# input_matrix.net
KiCad netlist of a schematic drawn in Altium Designer
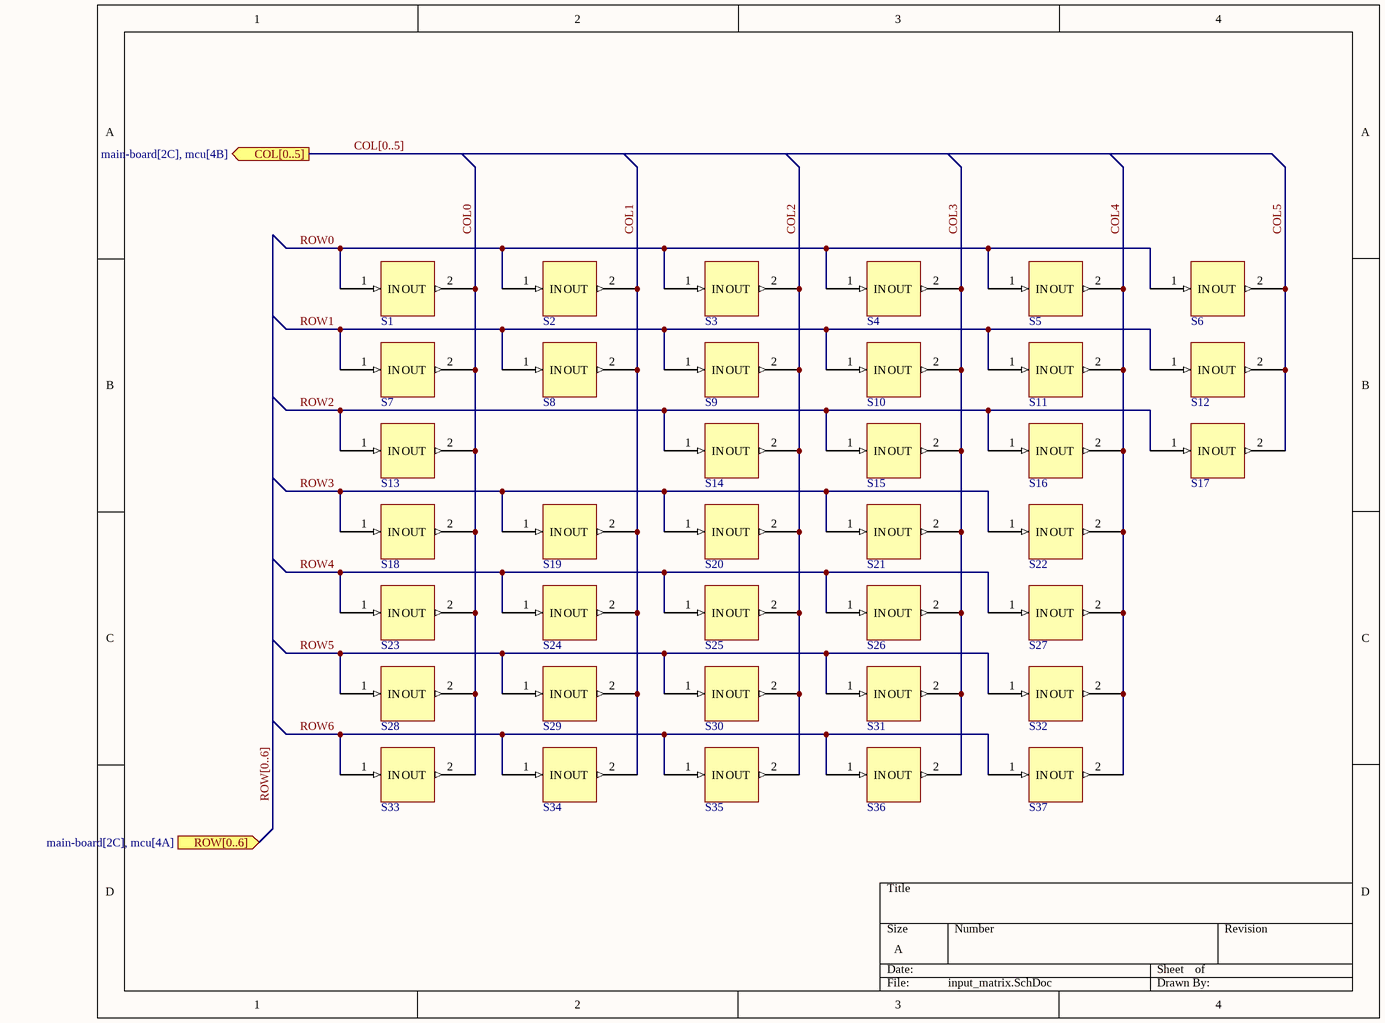
[diagram p0: input_matrix.SchDoc]

(export (version "E")
  (design (tool "Eeschema 10.0.6"))
  (components
    (comp (ref "S1")
      (value "temp_switch")
      (footprint "PCBComponent_1")
      (libsource (lib "button") (part "temp_switch"))
    )
    (comp (ref "S2")
      (value "temp_switch")
      (footprint "PCBComponent_1")
      (libsource (lib "button") (part "temp_switch"))
    )
    (comp (ref "S3")
      (value "temp_switch")
      (footprint "PCBComponent_1")
      (libsource (lib "button") (part "temp_switch"))
    )
    (comp (ref "S4")
      (value "temp_switch")
      (footprint "PCBComponent_1")
      (libsource (lib "button") (part "temp_switch"))
    )
    (comp (ref "S5")
      (value "temp_switch")
      (footprint "PCBComponent_1")
      (libsource (lib "button") (part "temp_switch"))
    )
    (comp (ref "S6")
      (value "temp_switch")
      (footprint "PCBComponent_1")
      (libsource (lib "button") (part "temp_switch"))
    )
    (comp (ref "S7")
      (value "temp_switch")
      (footprint "PCBComponent_1")
      (libsource (lib "button") (part "temp_switch"))
    )
    (comp (ref "S8")
      (value "temp_switch")
      (footprint "PCBComponent_1")
      (libsource (lib "button") (part "temp_switch"))
    )
    (comp (ref "S9")
      (value "temp_switch")
      (footprint "PCBComponent_1")
      (libsource (lib "button") (part "temp_switch"))
    )
    (comp (ref "S10")
      (value "temp_switch")
      (footprint "PCBComponent_1")
      (libsource (lib "button") (part "temp_switch"))
    )
    (comp (ref "S11")
      (value "temp_switch")
      (footprint "PCBComponent_1")
      (libsource (lib "button") (part "temp_switch"))
    )
    (comp (ref "S12")
      (value "temp_switch")
      (footprint "PCBComponent_1")
      (libsource (lib "button") (part "temp_switch"))
    )
    (comp (ref "S13")
      (value "temp_switch")
      (footprint "PCBComponent_1")
      (libsource (lib "button") (part "temp_switch"))
    )
    (comp (ref "S14")
      (value "temp_switch")
      (footprint "PCBComponent_1")
      (libsource (lib "button") (part "temp_switch"))
    )
    (comp (ref "S15")
      (value "temp_switch")
      (footprint "PCBComponent_1")
      (libsource (lib "button") (part "temp_switch"))
    )
    (comp (ref "S16")
      (value "temp_switch")
      (footprint "PCBComponent_1")
      (libsource (lib "button") (part "temp_switch"))
    )
    (comp (ref "S17")
      (value "temp_switch")
      (footprint "PCBComponent_1")
      (libsource (lib "button") (part "temp_switch"))
    )
    (comp (ref "S18")
      (value "temp_switch")
      (footprint "PCBComponent_1")
      (libsource (lib "button") (part "temp_switch"))
    )
    (comp (ref "S19")
      (value "temp_switch")
      (footprint "PCBComponent_1")
      (libsource (lib "button") (part "temp_switch"))
    )
    (comp (ref "S20")
      (value "temp_switch")
      (footprint "PCBComponent_1")
      (libsource (lib "button") (part "temp_switch"))
    )
    (comp (ref "S21")
      (value "temp_switch")
      (footprint "PCBComponent_1")
      (libsource (lib "button") (part "temp_switch"))
    )
    (comp (ref "S22")
      (value "temp_switch")
      (footprint "PCBComponent_1")
      (libsource (lib "button") (part "temp_switch"))
    )
    (comp (ref "S23")
      (value "temp_switch")
      (footprint "PCBComponent_1")
      (libsource (lib "button") (part "temp_switch"))
    )
    (comp (ref "S24")
      (value "temp_switch")
      (footprint "PCBComponent_1")
      (libsource (lib "button") (part "temp_switch"))
    )
    (comp (ref "S25")
      (value "temp_switch")
      (footprint "PCBComponent_1")
      (libsource (lib "button") (part "temp_switch"))
    )
    (comp (ref "S26")
      (value "temp_switch")
      (footprint "PCBComponent_1")
      (libsource (lib "button") (part "temp_switch"))
    )
    (comp (ref "S27")
      (value "temp_switch")
      (footprint "PCBComponent_1")
      (libsource (lib "button") (part "temp_switch"))
    )
    (comp (ref "S28")
      (value "temp_switch")
      (footprint "PCBComponent_1")
      (libsource (lib "button") (part "temp_switch"))
    )
    (comp (ref "S29")
      (value "temp_switch")
      (footprint "PCBComponent_1")
      (libsource (lib "button") (part "temp_switch"))
    )
    (comp (ref "S30")
      (value "temp_switch")
      (footprint "PCBComponent_1")
      (libsource (lib "button") (part "temp_switch"))
    )
    (comp (ref "S31")
      (value "temp_switch")
      (footprint "PCBComponent_1")
      (libsource (lib "button") (part "temp_switch"))
    )
    (comp (ref "S32")
      (value "temp_switch")
      (footprint "PCBComponent_1")
      (libsource (lib "button") (part "temp_switch"))
    )
    (comp (ref "S33")
      (value "temp_switch")
      (footprint "PCBComponent_1")
      (libsource (lib "button") (part "temp_switch"))
    )
    (comp (ref "S34")
      (value "temp_switch")
      (footprint "PCBComponent_1")
      (libsource (lib "button") (part "temp_switch"))
    )
    (comp (ref "S35")
      (value "temp_switch")
      (footprint "PCBComponent_1")
      (libsource (lib "button") (part "temp_switch"))
    )
    (comp (ref "S36")
      (value "temp_switch")
      (footprint "PCBComponent_1")
      (libsource (lib "button") (part "temp_switch"))
    )
    (comp (ref "S37")
      (value "temp_switch")
      (footprint "PCBComponent_1")
      (libsource (lib "button") (part "temp_switch"))
    )
  )
  (nets
    (net (code "1") (name "/COL0") (class "Default")
      (node (ref "S1") (pin "2") (pinfunction "OUT_2") (pintype "output"))
      (node (ref "S13") (pin "2") (pinfunction "OUT_2") (pintype "output"))
      (node (ref "S18") (pin "2") (pinfunction "OUT_2") (pintype "output"))
      (node (ref "S23") (pin "2") (pinfunction "OUT_2") (pintype "output"))
      (node (ref "S28") (pin "2") (pinfunction "OUT_2") (pintype "output"))
      (node (ref "S33") (pin "2") (pinfunction "OUT_2") (pintype "output"))
      (node (ref "S7") (pin "2") (pinfunction "OUT_2") (pintype "output"))
    )
    (net (code "2") (name "/COL1") (class "Default")
      (node (ref "S19") (pin "2") (pinfunction "OUT_2") (pintype "output"))
      (node (ref "S2") (pin "2") (pinfunction "OUT_2") (pintype "output"))
      (node (ref "S24") (pin "2") (pinfunction "OUT_2") (pintype "output"))
      (node (ref "S29") (pin "2") (pinfunction "OUT_2") (pintype "output"))
      (node (ref "S34") (pin "2") (pinfunction "OUT_2") (pintype "output"))
      (node (ref "S8") (pin "2") (pinfunction "OUT_2") (pintype "output"))
    )
    (net (code "3") (name "/COL2") (class "Default")
      (node (ref "S14") (pin "2") (pinfunction "OUT_2") (pintype "output"))
      (node (ref "S20") (pin "2") (pinfunction "OUT_2") (pintype "output"))
      (node (ref "S25") (pin "2") (pinfunction "OUT_2") (pintype "output"))
      (node (ref "S3") (pin "2") (pinfunction "OUT_2") (pintype "output"))
      (node (ref "S30") (pin "2") (pinfunction "OUT_2") (pintype "output"))
      (node (ref "S35") (pin "2") (pinfunction "OUT_2") (pintype "output"))
      (node (ref "S9") (pin "2") (pinfunction "OUT_2") (pintype "output"))
    )
    (net (code "4") (name "/COL3") (class "Default")
      (node (ref "S10") (pin "2") (pinfunction "OUT_2") (pintype "output"))
      (node (ref "S15") (pin "2") (pinfunction "OUT_2") (pintype "output"))
      (node (ref "S21") (pin "2") (pinfunction "OUT_2") (pintype "output"))
      (node (ref "S26") (pin "2") (pinfunction "OUT_2") (pintype "output"))
      (node (ref "S31") (pin "2") (pinfunction "OUT_2") (pintype "output"))
      (node (ref "S36") (pin "2") (pinfunction "OUT_2") (pintype "output"))
      (node (ref "S4") (pin "2") (pinfunction "OUT_2") (pintype "output"))
    )
    (net (code "5") (name "/COL4") (class "Default")
      (node (ref "S11") (pin "2") (pinfunction "OUT_2") (pintype "output"))
      (node (ref "S16") (pin "2") (pinfunction "OUT_2") (pintype "output"))
      (node (ref "S22") (pin "2") (pinfunction "OUT_2") (pintype "output"))
      (node (ref "S27") (pin "2") (pinfunction "OUT_2") (pintype "output"))
      (node (ref "S32") (pin "2") (pinfunction "OUT_2") (pintype "output"))
      (node (ref "S37") (pin "2") (pinfunction "OUT_2") (pintype "output"))
      (node (ref "S5") (pin "2") (pinfunction "OUT_2") (pintype "output"))
    )
    (net (code "6") (name "/COL5") (class "Default")
      (node (ref "S12") (pin "2") (pinfunction "OUT_2") (pintype "output"))
      (node (ref "S17") (pin "2") (pinfunction "OUT_2") (pintype "output"))
      (node (ref "S6") (pin "2") (pinfunction "OUT_2") (pintype "output"))
    )
    (net (code "8") (name "/ROW0") (class "Default")
      (node (ref "S1") (pin "1") (pinfunction "IN_1") (pintype "input"))
      (node (ref "S2") (pin "1") (pinfunction "IN_1") (pintype "input"))
      (node (ref "S3") (pin "1") (pinfunction "IN_1") (pintype "input"))
      (node (ref "S4") (pin "1") (pinfunction "IN_1") (pintype "input"))
      (node (ref "S5") (pin "1") (pinfunction "IN_1") (pintype "input"))
      (node (ref "S6") (pin "1") (pinfunction "IN_1") (pintype "input"))
    )
    (net (code "9") (name "/ROW1") (class "Default")
      (node (ref "S10") (pin "1") (pinfunction "IN_1") (pintype "input"))
      (node (ref "S11") (pin "1") (pinfunction "IN_1") (pintype "input"))
      (node (ref "S12") (pin "1") (pinfunction "IN_1") (pintype "input"))
      (node (ref "S7") (pin "1") (pinfunction "IN_1") (pintype "input"))
      (node (ref "S8") (pin "1") (pinfunction "IN_1") (pintype "input"))
      (node (ref "S9") (pin "1") (pinfunction "IN_1") (pintype "input"))
    )
    (net (code "10") (name "/ROW2") (class "Default")
      (node (ref "S13") (pin "1") (pinfunction "IN_1") (pintype "input"))
      (node (ref "S14") (pin "1") (pinfunction "IN_1") (pintype "input"))
      (node (ref "S15") (pin "1") (pinfunction "IN_1") (pintype "input"))
      (node (ref "S16") (pin "1") (pinfunction "IN_1") (pintype "input"))
      (node (ref "S17") (pin "1") (pinfunction "IN_1") (pintype "input"))
    )
    (net (code "11") (name "/ROW3") (class "Default")
      (node (ref "S18") (pin "1") (pinfunction "IN_1") (pintype "input"))
      (node (ref "S19") (pin "1") (pinfunction "IN_1") (pintype "input"))
      (node (ref "S20") (pin "1") (pinfunction "IN_1") (pintype "input"))
      (node (ref "S21") (pin "1") (pinfunction "IN_1") (pintype "input"))
      (node (ref "S22") (pin "1") (pinfunction "IN_1") (pintype "input"))
    )
    (net (code "12") (name "/ROW4") (class "Default")
      (node (ref "S23") (pin "1") (pinfunction "IN_1") (pintype "input"))
      (node (ref "S24") (pin "1") (pinfunction "IN_1") (pintype "input"))
      (node (ref "S25") (pin "1") (pinfunction "IN_1") (pintype "input"))
      (node (ref "S26") (pin "1") (pinfunction "IN_1") (pintype "input"))
      (node (ref "S27") (pin "1") (pinfunction "IN_1") (pintype "input"))
    )
    (net (code "13") (name "/ROW5") (class "Default")
      (node (ref "S28") (pin "1") (pinfunction "IN_1") (pintype "input"))
      (node (ref "S29") (pin "1") (pinfunction "IN_1") (pintype "input"))
      (node (ref "S30") (pin "1") (pinfunction "IN_1") (pintype "input"))
      (node (ref "S31") (pin "1") (pinfunction "IN_1") (pintype "input"))
      (node (ref "S32") (pin "1") (pinfunction "IN_1") (pintype "input"))
    )
    (net (code "14") (name "/ROW6") (class "Default")
      (node (ref "S33") (pin "1") (pinfunction "IN_1") (pintype "input"))
      (node (ref "S34") (pin "1") (pinfunction "IN_1") (pintype "input"))
      (node (ref "S35") (pin "1") (pinfunction "IN_1") (pintype "input"))
      (node (ref "S36") (pin "1") (pinfunction "IN_1") (pintype "input"))
      (node (ref "S37") (pin "1") (pinfunction "IN_1") (pintype "input"))
    )
  )
)
